# temperature_controller.net
KiCad netlist of a schematic drawn in Altium Designer
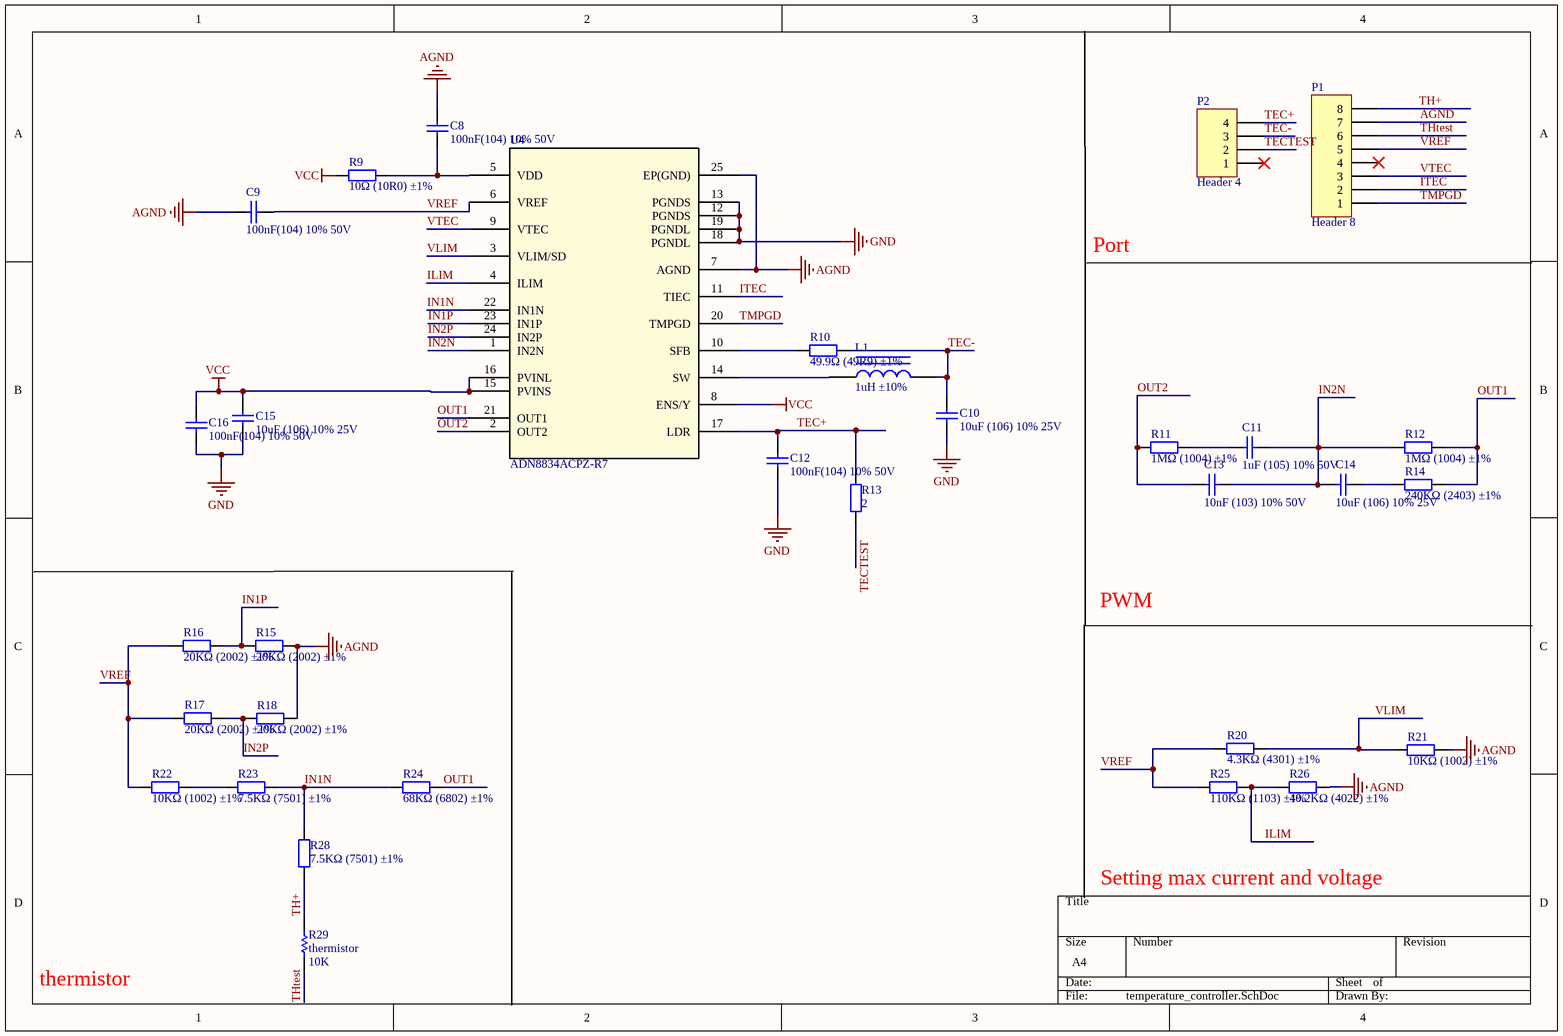
[diagram p0: temperature_controller.SchDoc]

(export (version "E")
  (design (tool "Eeschema 10.0.6"))
  (components
    (comp (ref "C8")
      (value "100nF(104) 10% 50V")
      (footprint "0805_C")
      (description "贴片电容")
      (libsource (lib "Cap") (part "0805 100nF(104) 10% 50V"))
    )
    (comp (ref "C9")
      (value "100nF(104) 10% 50V")
      (footprint "0805_C")
      (description "贴片电容")
      (libsource (lib "Cap") (part "0805 100nF(104) 10% 50V"))
    )
    (comp (ref "C10")
      (value "10uF (106) 10% 25V")
      (footprint "0805_C")
      (description "贴片电容")
      (libsource (lib "Cap") (part "0805 10uF (106) 10% 25V"))
    )
    (comp (ref "C11")
      (value "1uF (105) 10% 50V")
      (footprint "0805_C")
      (description "贴片电容")
      (libsource (lib "Cap") (part "0805 1uF (105) 10% 50V"))
    )
    (comp (ref "C12")
      (value "100nF(104) 10% 50V")
      (footprint "0805_C")
      (description "贴片电容")
      (libsource (lib "Cap") (part "0805 100nF(104) 10% 50V"))
    )
    (comp (ref "C13")
      (value "10nF (103) 10% 50V")
      (footprint "0805_C")
      (description "贴片电容")
      (libsource (lib "Cap") (part "0805 10nF (103) 10% 50V"))
    )
    (comp (ref "C14")
      (value "10uF (106) 10% 25V")
      (footprint "0805_C")
      (description "贴片电容")
      (libsource (lib "Cap") (part "0805 10uF (106) 10% 25V"))
    )
    (comp (ref "C15")
      (value "10uF (106) 10% 25V")
      (footprint "0805_C")
      (description "贴片电容")
      (libsource (lib "Cap") (part "0805 10uF (106) 10% 25V"))
    )
    (comp (ref "C16")
      (value "100nF(104) 10% 50V")
      (footprint "0805_C")
      (description "贴片电容")
      (libsource (lib "Cap") (part "0805 100nF(104) 10% 50V"))
    )
    (comp (ref "L1")
      (value "1uH ±10%")
      (footprint "0805_L")
      (description "贴片电感")
      (libsource (lib "IUD") (part "0805 1uH 10%"))
    )
    (comp (ref "P1")
      (value "Header 8")
      (footprint "HDR1X8")
      (description "Header, 8-Pin")
      (fields (field (name "PUBLISHER") "Altium Limited"))
      (libsource (lib "Miscellaneous Connectors") (part "Header 8"))
    )
    (comp (ref "P2")
      (value "Header 4")
      (footprint "HDR1X4")
      (description "Header, 4-Pin")
      (fields (field (name "PUBLISHER") "Altium Limited"))
      (libsource (lib "Miscellaneous Connectors") (part "Header 4"))
    )
    (comp (ref "R9")
      (value "10Ω (10R0) ±1%")
      (footprint "0603_R")
      (description "贴片电阻")
      (libsource (lib "RES") (part "0603 10Ω (10R0) 1%"))
    )
    (comp (ref "R10")
      (value "49.9Ω (49R9) ±1%")
      (footprint "0603_R")
      (description "贴片电阻")
      (libsource (lib "RES") (part "0603 49.9Ω (49R9) 1%"))
    )
    (comp (ref "R11")
      (value "1MΩ (1004) ±1%")
      (footprint "0603_R")
      (description "贴片电阻")
      (libsource (lib "RES") (part "0603 1MΩ (1004) 1%"))
    )
    (comp (ref "R12")
      (value "1MΩ (1004) ±1%")
      (footprint "0603_R")
      (description "贴片电阻")
      (libsource (lib "RES") (part "0603 1MΩ (1004) 1%"))
    )
    (comp (ref "R13")
      (value "2")
      (footprint "AXIAL-0.4")
      (description "Resistor")
      (fields (field (name "PUBLISHER") "Altium Limited"))
      (libsource (lib "Miscellaneous Devices") (part "Res2"))
    )
    (comp (ref "R14")
      (value "240KΩ (2403) ±1%")
      (footprint "0603_R")
      (description "贴片电阻")
      (libsource (lib "RES") (part "0603 240KΩ (2403) 1%"))
    )
    (comp (ref "R15")
      (value "20KΩ (2002) ±1%")
      (footprint "0603_R")
      (description "贴片电阻")
      (libsource (lib "RES") (part "0603 20KΩ (2002) 1%"))
    )
    (comp (ref "R16")
      (value "20KΩ (2002) ±1%")
      (footprint "0603_R")
      (description "贴片电阻")
      (libsource (lib "") (part "0603 20KΩ (2002) 1%_1"))
    )
    (comp (ref "R17")
      (value "20KΩ (2002) ±1%")
      (footprint "0603_R")
      (description "贴片电阻")
      (libsource (lib "RES") (part "0603 20KΩ (2002) 1%"))
    )
    (comp (ref "R18")
      (value "20KΩ (2002) ±1%")
      (footprint "0603_R")
      (description "贴片电阻")
      (libsource (lib "RES") (part "0603 20KΩ (2002) 1%"))
    )
    (comp (ref "R20")
      (value "4.3KΩ (4301) ±1%")
      (footprint "0603_R")
      (description "贴片电阻")
      (libsource (lib "RES") (part "0603 4.3KΩ (4301) 1%"))
    )
    (comp (ref "R21")
      (value "10KΩ (1002) ±1%")
      (footprint "0603_R")
      (description "贴片电阻")
      (libsource (lib "") (part "0603 10KΩ (1002) 1%_1"))
    )
    (comp (ref "R22")
      (value "10KΩ (1002) ±1%")
      (footprint "0603_R")
      (description "贴片电阻")
      (libsource (lib "RES") (part "0603 10KΩ (1002) 1%"))
    )
    (comp (ref "R23")
      (value "7.5KΩ (7501) ±1%")
      (footprint "0603_R")
      (description "贴片电阻")
      (libsource (lib "") (part "0603 7.5KΩ (7501) 1%_1"))
    )
    (comp (ref "R24")
      (value "68KΩ (6802) ±1%")
      (footprint "0603_R")
      (description "贴片电阻")
      (libsource (lib "RES") (part "0603 68KΩ (6802) 1%"))
    )
    (comp (ref "R25")
      (value "110KΩ (1103) ±1%")
      (footprint "0603_R")
      (description "贴片电阻")
      (libsource (lib "RES") (part "0603 110KΩ (1103) 1%"))
    )
    (comp (ref "R26")
      (value "40.2KΩ (4022) ±1%")
      (footprint "0603_R")
      (description "贴片电阻")
      (libsource (lib "RES") (part "0603 40.2KΩ (4022) 1%"))
    )
    (comp (ref "R28")
      (value "7.5KΩ (7501) ±1%")
      (footprint "0603_R")
      (description "贴片电阻")
      (libsource (lib "RES") (part "0603 7.5KΩ (7501) 1%"))
    )
    (comp (ref "R29")
      (value "thermistor")
      (footprint "AXIAL-0.3")
      (description "thermistor 1%")
      (fields (field (name "ALTIUM_VALUE") "10K") (field (name "PUBLISHER") "Altium Limited"))
      (libsource (lib "Miscellaneous Devices") (part "Res1"))
    )
    (comp (ref "U4")
      (value "ADN8834ACPZ-R7")
      (footprint "CP_24_7")
      (description "No Description Available")
      (fields (field (name "COPYRIGHT") "Copyright (C) 2018 Accelerated Designs. All rights reserved"))
      (libsource (lib "2020-07-09_16-32-34") (part "ADN8834ACPZ-R7"))
    )
  )
  (nets
    (net (code "1") (name "/ILIM") (class "Default")
      (node (ref "R26") (pin "1") (pinfunction "1_1") (pintype "passive"))
      (node (ref "U4") (pin "4") (pinfunction "ILIM_4") (pintype "passive"))
    )
    (net (code "2") (name "/IN1N") (class "Default")
      (node (ref "R23") (pin "1") (pinfunction "1_1") (pintype "passive"))
      (node (ref "R24") (pin "2") (pinfunction "2_2") (pintype "passive"))
      (node (ref "R28") (pin "2") (pinfunction "2_2") (pintype "passive"))
      (node (ref "U4") (pin "22") (pinfunction "IN1N_22") (pintype "passive"))
    )
    (net (code "3") (name "/IN1P") (class "Default")
      (node (ref "R15") (pin "2") (pinfunction "2_2") (pintype "passive"))
      (node (ref "R16") (pin "2") (pinfunction "2_2") (pintype "passive"))
      (node (ref "U4") (pin "23") (pinfunction "IN1P_23") (pintype "passive"))
    )
    (net (code "4") (name "/IN2N") (class "Default")
      (node (ref "C11") (pin "1") (pinfunction "1_1") (pintype "passive"))
      (node (ref "C13") (pin "1") (pinfunction "1_1") (pintype "passive"))
      (node (ref "C14") (pin "2") (pinfunction "2_2") (pintype "passive"))
      (node (ref "R12") (pin "1") (pinfunction "1_1") (pintype "passive"))
      (node (ref "U4") (pin "1") (pinfunction "IN2N_1") (pintype "passive"))
    )
    (net (code "5") (name "/IN2P") (class "Default")
      (node (ref "R17") (pin "1") (pinfunction "1_1") (pintype "passive"))
      (node (ref "R18") (pin "2") (pinfunction "2_2") (pintype "passive"))
      (node (ref "U4") (pin "24") (pinfunction "IN2P_24") (pintype "passive"))
    )
    (net (code "6") (name "/ITEC") (class "Default")
      (node (ref "P1") (pin "2") (pinfunction "2_2") (pintype "passive"))
      (node (ref "U4") (pin "11") (pinfunction "TIEC_11") (pintype "passive"))
    )
    (net (code "7") (name "/OUT1") (class "Default")
      (node (ref "R12") (pin "2") (pinfunction "2_2") (pintype "passive"))
      (node (ref "R14") (pin "2") (pinfunction "2_2") (pintype "passive"))
      (node (ref "R24") (pin "1") (pinfunction "1_1") (pintype "passive"))
      (node (ref "U4") (pin "21") (pinfunction "OUT1_21") (pintype "passive"))
    )
    (net (code "8") (name "/OUT2") (class "Default")
      (node (ref "C13") (pin "2") (pinfunction "2_2") (pintype "passive"))
      (node (ref "R11") (pin "1") (pinfunction "1_1") (pintype "passive"))
      (node (ref "U4") (pin "2") (pinfunction "OUT2_2") (pintype "passive"))
    )
    (net (code "9") (name "/TEC+") (class "Default")
      (node (ref "C12") (pin "2") (pinfunction "2_2") (pintype "passive"))
      (node (ref "P2") (pin "4") (pinfunction "4_4") (pintype "passive"))
      (node (ref "R13") (pin "2") (pinfunction "2_2") (pintype "passive"))
      (node (ref "U4") (pin "17") (pinfunction "LDR_17") (pintype "passive"))
    )
    (net (code "10") (name "/TEC-") (class "Default")
      (node (ref "C10") (pin "1") (pinfunction "1_1") (pintype "passive"))
      (node (ref "L1") (pin "2") (pinfunction "2_2") (pintype "passive"))
      (node (ref "P2") (pin "3") (pinfunction "3_3") (pintype "passive"))
      (node (ref "R10") (pin "2") (pinfunction "2_2") (pintype "passive"))
    )
    (net (code "11") (name "/TECTEST") (class "Default")
      (node (ref "P2") (pin "2") (pinfunction "2_2") (pintype "passive"))
      (node (ref "R13") (pin "1") (pinfunction "1_1") (pintype "passive"))
    )
    (net (code "12") (name "/TH+") (class "Default")
      (node (ref "P1") (pin "8") (pinfunction "8_8") (pintype "passive"))
      (node (ref "R28") (pin "1") (pinfunction "1_1") (pintype "passive"))
      (node (ref "R29") (pin "2") (pinfunction "2_2") (pintype "passive"))
    )
    (net (code "13") (name "/THtest") (class "Default")
      (node (ref "P1") (pin "6") (pinfunction "6_6") (pintype "passive"))
      (node (ref "R29") (pin "1") (pinfunction "1_1") (pintype "passive"))
    )
    (net (code "14") (name "/TMPGD") (class "Default")
      (node (ref "P1") (pin "1") (pinfunction "1_1") (pintype "passive"))
      (node (ref "U4") (pin "20") (pinfunction "TMPGD_20") (pintype "passive"))
    )
    (net (code "15") (name "/VLIM") (class "Default")
      (node (ref "R20") (pin "2") (pinfunction "2_2") (pintype "passive"))
      (node (ref "R21") (pin "1") (pinfunction "1_1") (pintype "passive"))
      (node (ref "U4") (pin "3") (pinfunction "VLIM/SD_3") (pintype "passive"))
    )
    (net (code "16") (name "/VREF") (class "Default")
      (node (ref "C9") (pin "1") (pinfunction "1_1") (pintype "passive"))
      (node (ref "P1") (pin "5") (pinfunction "5_5") (pintype "passive"))
      (node (ref "R16") (pin "1") (pinfunction "1_1") (pintype "passive"))
      (node (ref "R17") (pin "2") (pinfunction "2_2") (pintype "passive"))
      (node (ref "R20") (pin "1") (pinfunction "1_1") (pintype "passive"))
      (node (ref "R22") (pin "2") (pinfunction "2_2") (pintype "passive"))
      (node (ref "R25") (pin "1") (pinfunction "1_1") (pintype "passive"))
      (node (ref "U4") (pin "6") (pinfunction "VREF_6") (pintype "passive"))
    )
    (net (code "17") (name "/VTEC") (class "Default")
      (node (ref "P1") (pin "3") (pinfunction "3_3") (pintype "passive"))
      (node (ref "U4") (pin "9") (pinfunction "VTEC_9") (pintype "passive"))
    )
    (net (code "18") (name "AGND") (class "Default")
      (node (ref "C8") (pin "2") (pinfunction "2_2") (pintype "passive"))
      (node (ref "C9") (pin "2") (pinfunction "2_2") (pintype "passive"))
      (node (ref "P1") (pin "7") (pinfunction "7_7") (pintype "passive"))
      (node (ref "R15") (pin "1") (pinfunction "1_1") (pintype "passive"))
      (node (ref "R18") (pin "1") (pinfunction "1_1") (pintype "passive"))
      (node (ref "R21") (pin "2") (pinfunction "2_2") (pintype "passive"))
      (node (ref "R26") (pin "2") (pinfunction "2_2") (pintype "passive"))
      (node (ref "U4") (pin "25") (pinfunction "EP(GND)_25") (pintype "passive"))
      (node (ref "U4") (pin "7") (pinfunction "AGND_7") (pintype "passive"))
    )
    (net (code "19") (name "GND") (class "Default")
      (node (ref "C10") (pin "2") (pinfunction "2_2") (pintype "passive"))
      (node (ref "C12") (pin "1") (pinfunction "1_1") (pintype "passive"))
      (node (ref "C15") (pin "2") (pinfunction "2_2") (pintype "passive"))
      (node (ref "C16") (pin "2") (pinfunction "2_2") (pintype "passive"))
      (node (ref "U4") (pin "12") (pinfunction "PGNDS_12") (pintype "passive"))
      (node (ref "U4") (pin "13") (pinfunction "PGNDS_13") (pintype "passive"))
      (node (ref "U4") (pin "18") (pinfunction "PGNDL_18") (pintype "passive"))
      (node (ref "U4") (pin "19") (pinfunction "PGNDL_19") (pintype "passive"))
    )
    (net (code "20") (name "Net-(C11-Pad2)") (class "Default")
      (node (ref "C11") (pin "2") (pinfunction "2_2") (pintype "passive"))
      (node (ref "R11") (pin "2") (pinfunction "2_2") (pintype "passive"))
    )
    (net (code "21") (name "Net-(C14-Pad1)") (class "Default")
      (node (ref "C14") (pin "1") (pinfunction "1_1") (pintype "passive"))
      (node (ref "R14") (pin "1") (pinfunction "1_1") (pintype "passive"))
    )
    (net (code "22") (name "Net-(R22-Pad1)") (class "Default")
      (node (ref "R22") (pin "1") (pinfunction "1_1") (pintype "passive"))
      (node (ref "R23") (pin "2") (pinfunction "2_2") (pintype "passive"))
    )
    (net (code "23") (name "Net-(U4-SFB)") (class "Default")
      (node (ref "R10") (pin "1") (pinfunction "1_1") (pintype "passive"))
      (node (ref "U4") (pin "10") (pinfunction "SFB_10") (pintype "passive"))
    )
    (net (code "24") (name "Net-(U4-SW)") (class "Default")
      (node (ref "L1") (pin "1") (pinfunction "1_1") (pintype "passive"))
      (node (ref "U4") (pin "14") (pinfunction "SW_14") (pintype "passive"))
    )
    (net (code "25") (name "Net-(U4-VDD)") (class "Default")
      (node (ref "C8") (pin "1") (pinfunction "1_1") (pintype "passive"))
      (node (ref "R9") (pin "2") (pinfunction "2_2") (pintype "passive"))
      (node (ref "U4") (pin "5") (pinfunction "VDD_5") (pintype "passive"))
    )
    (net (code "26") (name "VCC") (class "Default")
      (node (ref "C15") (pin "1") (pinfunction "1_1") (pintype "passive"))
      (node (ref "C16") (pin "1") (pinfunction "1_1") (pintype "passive"))
      (node (ref "R9") (pin "1") (pinfunction "1_1") (pintype "passive"))
      (node (ref "U4") (pin "15") (pinfunction "PVINS_15") (pintype "passive"))
      (node (ref "U4") (pin "16") (pinfunction "PVINL_16") (pintype "passive"))
      (node (ref "U4") (pin "8") (pinfunction "ENS/Y_8") (pintype "passive"))
    )
    (net (code "27") (name "unconnected-(P1-Pad4)") (class "Default")
      (node (ref "P1") (pin "4") (pinfunction "4_4") (pintype "passive+no_connect"))
    )
    (net (code "28") (name "unconnected-(P2-Pad1)") (class "Default")
      (node (ref "P2") (pin "1") (pinfunction "1_1") (pintype "passive+no_connect"))
    )
    (net (code "29") (name "unconnected-(R25-Pad2)") (class "Default")
      (node (ref "R25") (pin "2") (pinfunction "2_2") (pintype "passive"))
    )
  )
)
